# Microcontroller.net
KiCad netlist of a schematic drawn in Altium Designer
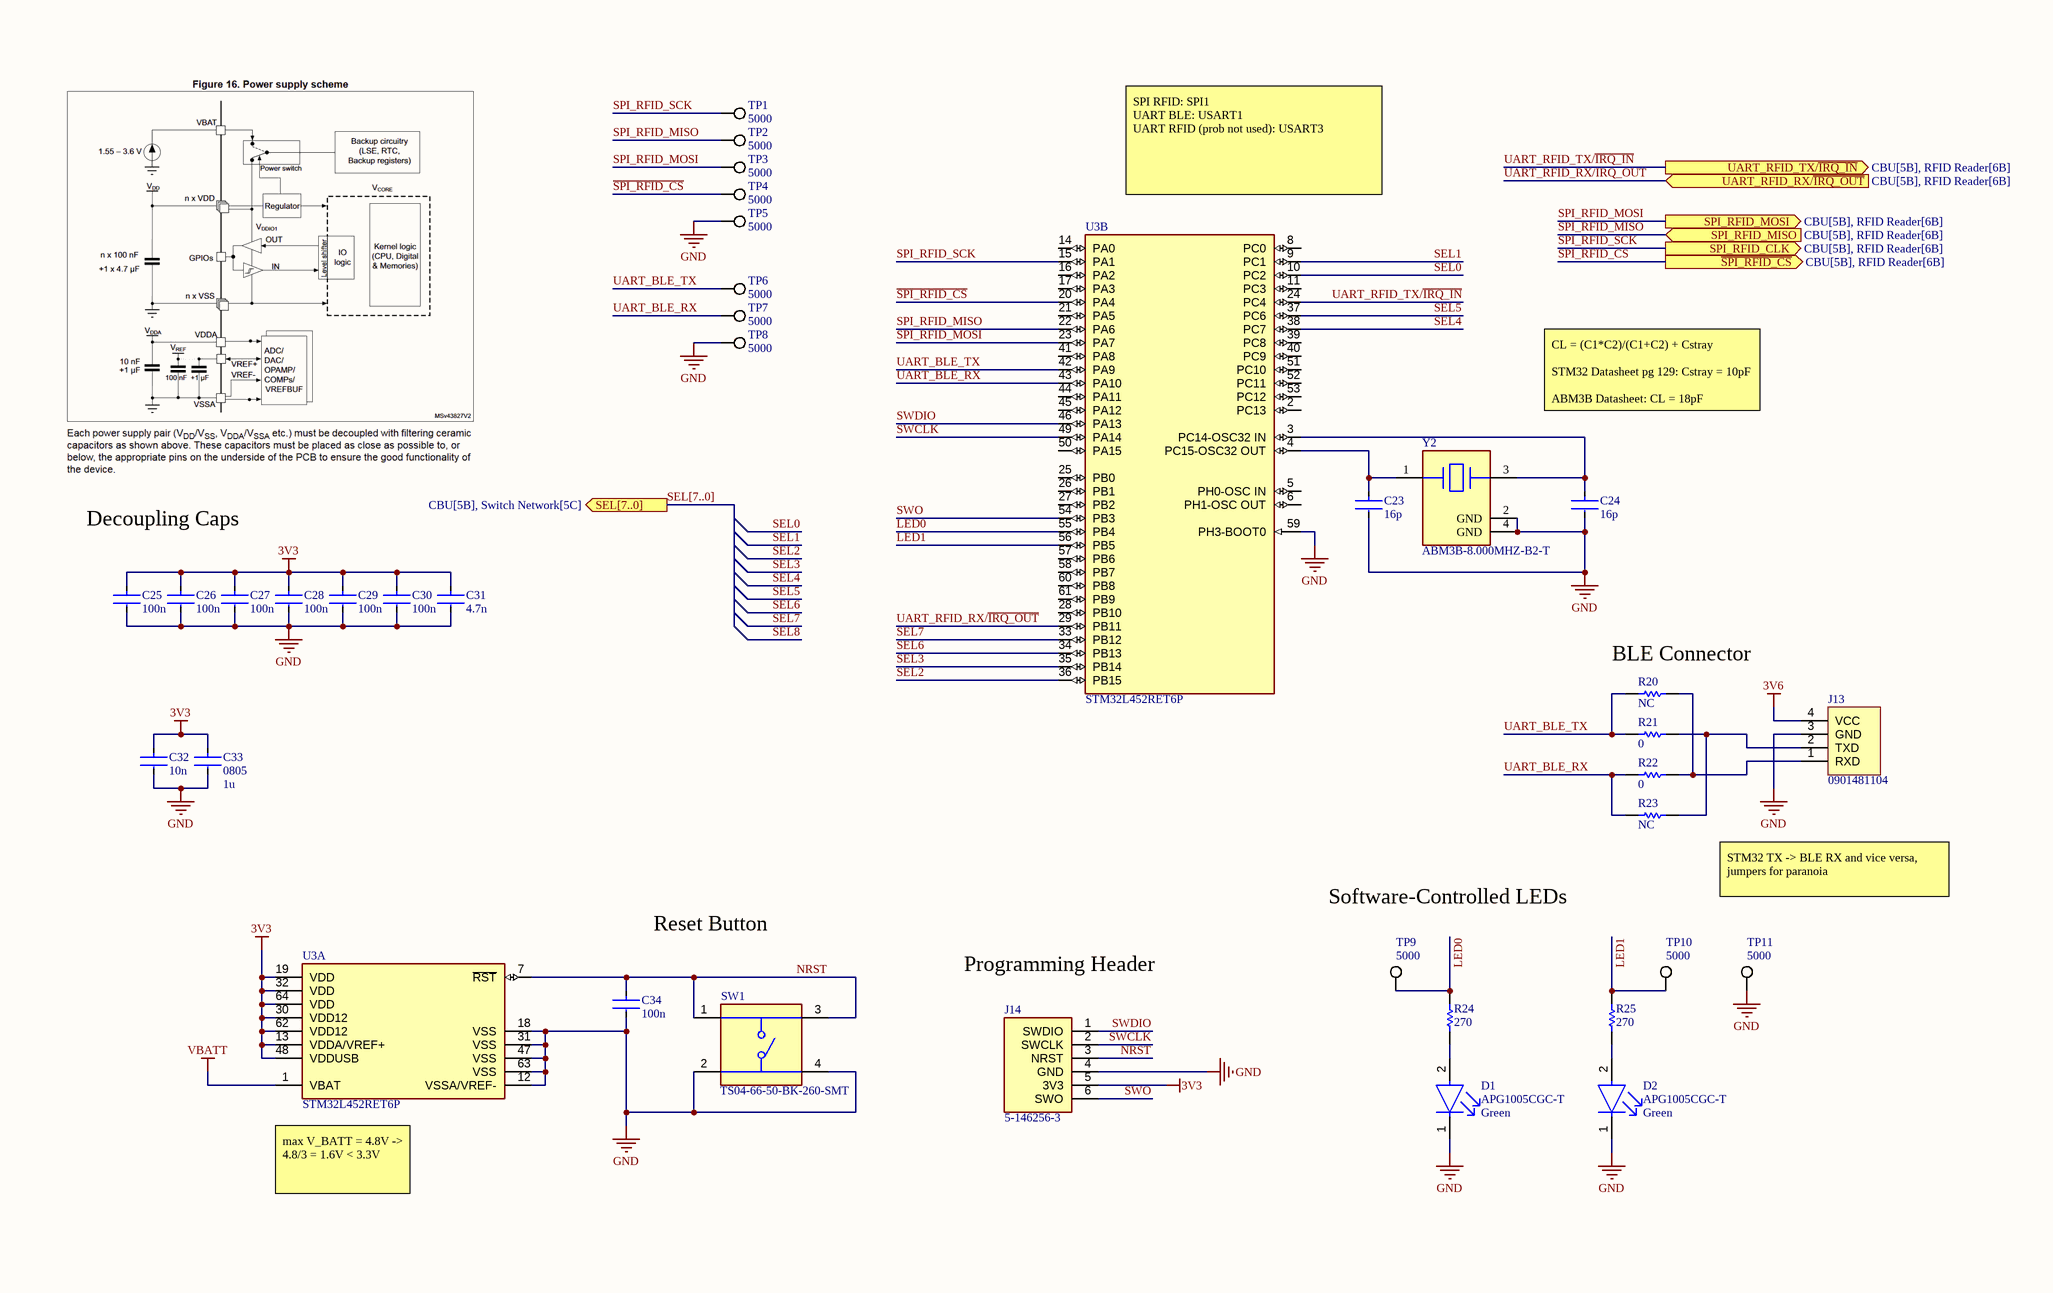
[diagram p0: Microcontroller.SchDoc]

(export (version "E")
  (design (tool "Eeschema 10.0.6"))
  (components
    (comp (ref "C23")
      (value "16p")
      (footprint "FP-0603-Capacitor-CL10-IPC_B")
      (description "CAP CER 50V X7R 0603")
      (fields (field (name "TOLERANCE") "0.1") (field (name "MANUFACTURER") "KEMET"))
      (libsource (lib "CBU-PCB") (part "Ceramic Capacitor 0603"))
    )
    (comp (ref "C24")
      (value "16p")
      (footprint "FP-0603-Capacitor-CL10-IPC_B")
      (description "CAP CER 50V X7R 0603")
      (fields (field (name "TOLERANCE") "0.1") (field (name "MANUFACTURER") "KEMET"))
      (libsource (lib "CBU-PCB") (part "Ceramic Capacitor 0603"))
    )
    (comp (ref "C25")
      (value "100n")
      (footprint "FP-0603-Capacitor-CL10-IPC_B")
      (description "CAP CER 50V X7R 0603")
      (fields (field (name "TOLERANCE") "0.1") (field (name "MANUFACTURER") "KEMET"))
      (libsource (lib "CBU-PCB") (part "Ceramic Capacitor 0603"))
    )
    (comp (ref "C26")
      (value "100n")
      (footprint "FP-0603-Capacitor-CL10-IPC_B")
      (description "CAP CER 50V X7R 0603")
      (fields (field (name "TOLERANCE") "0.1") (field (name "MANUFACTURER") "KEMET"))
      (libsource (lib "CBU-PCB") (part "Ceramic Capacitor 0603"))
    )
    (comp (ref "C27")
      (value "100n")
      (footprint "FP-0603-Capacitor-CL10-IPC_B")
      (description "CAP CER 50V X7R 0603")
      (fields (field (name "TOLERANCE") "0.1") (field (name "MANUFACTURER") "KEMET"))
      (libsource (lib "CBU-PCB") (part "Ceramic Capacitor 0603"))
    )
    (comp (ref "C28")
      (value "100n")
      (footprint "FP-0603-Capacitor-CL10-IPC_B")
      (description "CAP CER 50V X7R 0603")
      (fields (field (name "TOLERANCE") "0.1") (field (name "MANUFACTURER") "KEMET"))
      (libsource (lib "CBU-PCB") (part "Ceramic Capacitor 0603"))
    )
    (comp (ref "C29")
      (value "100n")
      (footprint "FP-0603-Capacitor-CL10-IPC_B")
      (description "CAP CER 50V X7R 0603")
      (fields (field (name "TOLERANCE") "0.1") (field (name "MANUFACTURER") "KEMET"))
      (libsource (lib "CBU-PCB") (part "Ceramic Capacitor 0603"))
    )
    (comp (ref "C30")
      (value "100n")
      (footprint "FP-0603-Capacitor-CL10-IPC_B")
      (description "CAP CER 50V X7R 0603")
      (fields (field (name "TOLERANCE") "0.1") (field (name "MANUFACTURER") "KEMET"))
      (libsource (lib "CBU-PCB") (part "Ceramic Capacitor 0603"))
    )
    (comp (ref "C31")
      (value "4.7n")
      (footprint "FP-0603-Capacitor-CL10-IPC_B")
      (description "CAP CER 50V X7R 0603")
      (fields (field (name "TOLERANCE") "0.1") (field (name "MANUFACTURER") "KEMET"))
      (libsource (lib "CBU-PCB") (part "Ceramic Capacitor 0603"))
    )
    (comp (ref "C32")
      (value "10n")
      (footprint "FP-0603-Capacitor-CL10-IPC_B")
      (description "CAP CER 50V X7R 0603")
      (fields (field (name "TOLERANCE") "0.1") (field (name "MANUFACTURER") "KEMET"))
      (libsource (lib "CBU-PCB") (part "Ceramic Capacitor 0603"))
    )
    (comp (ref "C33")
      (value "1u")
      (footprint "FP-0805-Capacitor-CL21-IPC_B")
      (description "CAP CER 50V X7R 0805")
      (fields
        (field (name "TOLERANCE") "0.1")
        (field (name "MANUFACTURER") "KEMET")
        (field (name "PACKAGE") "0805")
      )
      (libsource (lib "CBU-PCB") (part "Ceramic Capacitor 0805"))
    )
    (comp (ref "C34")
      (value "100n")
      (footprint "FP-0603-Capacitor-CL10-IPC_B")
      (description "CAP CER 50V X7R 0603")
      (fields (field (name "TOLERANCE") "0.1") (field (name "MANUFACTURER") "KEMET"))
      (libsource (lib "CBU-PCB") (part "Ceramic Capacitor 0603"))
    )
    (comp (ref "D1")
      (value "APG1005CGC-T")
      (footprint "FP-APG1005CGC-T-MFG")
      (description "LED GREEN CLEAR CHIP SMD")
      (fields (field (name "COLOR") "Green"))
      (libsource (lib "CBU-PCB") (part "APG1005CGC-T"))
    )
    (comp (ref "D2")
      (value "APG1005CGC-T")
      (footprint "FP-APG1005CGC-T-MFG")
      (description "LED GREEN CLEAR CHIP SMD")
      (fields (field (name "COLOR") "Green"))
      (libsource (lib "CBU-PCB") (part "APG1005CGC-T"))
    )
    (comp (ref "J13")
      (value "0901481104")
      (footprint "0901481104")
      (libsource (lib "CBU-PCB") (part "0901481104"))
    )
    (comp (ref "J14")
      (value "5-146256-3")
      (footprint "TE_5-146256-3")
      (description "Header; Breakaway; 0.100 x 0.100 in.; PC Board; Dual; 6; 0.025 in.; 0.12 in.")
      (fields (field (name "MF") "TE Connectivity") (field (name "DIGI-KEY_PART_NUMBER") "A121369-ND"))
      (libsource (lib "CBU-PCB") (part "5-146256-3"))
    )
    (comp (ref "R20")
      (value "NC")
      (footprint "RESC1608X55X25NL10T15")
      (fields
        (field (name "TOLERANCE") "1%")
        (field (name "MANUFACTURER") "Yageo")
        (field (name "Comment") "RC0603FR-072K2L")
      )
      (libsource (lib "CBU-PCB") (part "Resistor 0603"))
    )
    (comp (ref "R21")
      (value "0")
      (footprint "RESC1608X55X25NL10T15")
      (fields
        (field (name "TOLERANCE") "1%")
        (field (name "MANUFACTURER") "Yageo")
        (field (name "Comment") "RC0603FR-072K2L")
      )
      (libsource (lib "CBU-PCB") (part "Resistor 0603"))
    )
    (comp (ref "R22")
      (value "0")
      (footprint "RESC1608X55X25NL10T15")
      (fields
        (field (name "TOLERANCE") "1%")
        (field (name "MANUFACTURER") "Yageo")
        (field (name "Comment") "RC0603FR-072K2L")
      )
      (libsource (lib "CBU-PCB") (part "Resistor 0603"))
    )
    (comp (ref "R23")
      (value "NC")
      (footprint "RESC1608X55X25NL10T15")
      (fields
        (field (name "TOLERANCE") "1%")
        (field (name "MANUFACTURER") "Yageo")
        (field (name "Comment") "RC0603FR-072K2L")
      )
      (libsource (lib "CBU-PCB") (part "Resistor 0603"))
    )
    (comp (ref "R24")
      (value "270")
      (footprint "RESC1608X55X25NL10T15")
      (fields
        (field (name "TOLERANCE") "1%")
        (field (name "MANUFACTURER") "Yageo")
        (field (name "Comment") "RC0603FR-072K2L")
      )
      (libsource (lib "CBU-PCB") (part "Resistor 0603"))
    )
    (comp (ref "R25")
      (value "270")
      (footprint "RESC1608X55X25NL10T15")
      (fields
        (field (name "TOLERANCE") "1%")
        (field (name "MANUFACTURER") "Yageo")
        (field (name "Comment") "RC0603FR-072K2L")
      )
      (libsource (lib "CBU-PCB") (part "Resistor 0603"))
    )
    (comp (ref "SW1")
      (value "TS04-66-50-BK-260-SMT")
      (footprint "SW_TS04-66-50-BK-260-SMT")
      (description "Tactile Switch SPST-NO Top Actuated Surface Mount")
      (libsource (lib "CBU-PCB") (part "TS04-66-50-BK-260-SMT"))
    )
    (comp (ref "TP1")
      (value "5000")
      (footprint "FP-5000-MFG")
      (description "Red PC Test Point, Miniature Phosphor Bronze Silver Plating Through Hole Mounting Type")
      (libsource (lib "CBU-PCB") (part "5000"))
    )
    (comp (ref "TP2")
      (value "5000")
      (footprint "FP-5000-MFG")
      (description "Red PC Test Point, Miniature Phosphor Bronze Silver Plating Through Hole Mounting Type")
      (libsource (lib "CBU-PCB") (part "5000"))
    )
    (comp (ref "TP3")
      (value "5000")
      (footprint "FP-5000-MFG")
      (description "Red PC Test Point, Miniature Phosphor Bronze Silver Plating Through Hole Mounting Type")
      (libsource (lib "CBU-PCB") (part "5000"))
    )
    (comp (ref "TP4")
      (value "5000")
      (footprint "FP-5000-MFG")
      (description "Red PC Test Point, Miniature Phosphor Bronze Silver Plating Through Hole Mounting Type")
      (libsource (lib "CBU-PCB") (part "5000"))
    )
    (comp (ref "TP5")
      (value "5000")
      (footprint "FP-5000-MFG")
      (description "Red PC Test Point, Miniature Phosphor Bronze Silver Plating Through Hole Mounting Type")
      (libsource (lib "CBU-PCB") (part "5000"))
    )
    (comp (ref "TP6")
      (value "5000")
      (footprint "FP-5000-MFG")
      (description "Red PC Test Point, Miniature Phosphor Bronze Silver Plating Through Hole Mounting Type")
      (libsource (lib "CBU-PCB") (part "5000"))
    )
    (comp (ref "TP7")
      (value "5000")
      (footprint "FP-5000-MFG")
      (description "Red PC Test Point, Miniature Phosphor Bronze Silver Plating Through Hole Mounting Type")
      (libsource (lib "CBU-PCB") (part "5000"))
    )
    (comp (ref "TP8")
      (value "5000")
      (footprint "FP-5000-MFG")
      (description "Red PC Test Point, Miniature Phosphor Bronze Silver Plating Through Hole Mounting Type")
      (libsource (lib "CBU-PCB") (part "5000"))
    )
    (comp (ref "TP9")
      (value "5000")
      (footprint "FP-5000-MFG")
      (description "Red PC Test Point, Miniature Phosphor Bronze Silver Plating Through Hole Mounting Type")
      (libsource (lib "CBU-PCB") (part "5000"))
    )
    (comp (ref "TP10")
      (value "5000")
      (footprint "FP-5000-MFG")
      (description "Red PC Test Point, Miniature Phosphor Bronze Silver Plating Through Hole Mounting Type")
      (libsource (lib "CBU-PCB") (part "5000"))
    )
    (comp (ref "TP11")
      (value "5000")
      (footprint "FP-5000-MFG")
      (description "Red PC Test Point, Miniature Phosphor Bronze Silver Plating Through Hole Mounting Type")
      (libsource (lib "CBU-PCB") (part "5000"))
    )
    (comp (ref "U3")
      (value "STM32L452RET6P")
      (footprint "FP-STM32L452RET6P-MFG")
      (description "IC MCU 32BIT 512KB FLASH 64LQFP")
      (fields
        (field (name "OCTOPART") "https://octopart.com/stm32l452ret6p-stmicroelectronics-82945027")
        (field (name "MANUFACTURER") "STMicroelectronics")
      )
      (libsource (lib "CBU-PCB") (part "STM32L452RET6P"))
    )
    (comp (ref "Y2")
      (value "ABM3B-8.000MHZ-B2-T")
      (footprint "FP-ABM3B-MFG")
      (description "Crystal 8MHz ±20ppm 18pF SMD-4 5mm x 3.2mm")
      (fields (field (name "TOLERANCE") "20ppm"))
      (libsource (lib "CBU-PCB") (part "ABM3B-8.000MHZ-B2-T"))
    )
  )
  (nets
    (net (code "1") (name "/LED0") (class "Default")
      (node (ref "R24") (pin "2") (pinfunction "2_2") (pintype "passive"))
      (node (ref "TP9") (pin "1") (pinfunction "1_1") (pintype "passive"))
      (node (ref "U3") (pin "55") (pinfunction "PB4_55") (pintype "bidirectional"))
    )
    (net (code "2") (name "/LED1") (class "Default")
      (node (ref "R25") (pin "2") (pinfunction "2_2") (pintype "passive"))
      (node (ref "TP10") (pin "1") (pinfunction "1_1") (pintype "passive"))
      (node (ref "U3") (pin "56") (pinfunction "PB5_56") (pintype "bidirectional"))
    )
    (net (code "3") (name "/NRST") (class "Default")
      (node (ref "C34") (pin "1") (pinfunction "1_1") (pintype "passive"))
      (node (ref "J14") (pin "3") (pinfunction "NRST_3") (pintype "passive"))
      (node (ref "SW1") (pin "1") (pinfunction "1_1") (pintype "passive"))
      (node (ref "SW1") (pin "3") (pinfunction "3_3") (pintype "passive"))
      (node (ref "U3") (pin "7") (pinfunction "~{RST}_7") (pintype "bidirectional"))
    )
    (net (code "4") (name "/SEL0") (class "Default")
      (node (ref "U3") (pin "10") (pinfunction "PC2_10") (pintype "bidirectional"))
    )
    (net (code "5") (name "/SEL1") (class "Default")
      (node (ref "U3") (pin "9") (pinfunction "PC1_9") (pintype "bidirectional"))
    )
    (net (code "6") (name "/SEL2") (class "Default")
      (node (ref "U3") (pin "36") (pinfunction "PB15_36") (pintype "bidirectional"))
    )
    (net (code "7") (name "/SEL3") (class "Default")
      (node (ref "U3") (pin "35") (pinfunction "PB14_35") (pintype "bidirectional"))
    )
    (net (code "8") (name "/SEL4") (class "Default")
      (node (ref "U3") (pin "38") (pinfunction "PC7_38") (pintype "bidirectional"))
    )
    (net (code "9") (name "/SEL5") (class "Default")
      (node (ref "U3") (pin "37") (pinfunction "PC6_37") (pintype "bidirectional"))
    )
    (net (code "10") (name "/SEL6") (class "Default")
      (node (ref "U3") (pin "34") (pinfunction "PB13_34") (pintype "bidirectional"))
    )
    (net (code "11") (name "/SEL7") (class "Default")
      (node (ref "U3") (pin "33") (pinfunction "PB12_33") (pintype "bidirectional"))
    )
    (net (code "14") (name "/SPI_RFID_MISO") (class "Default")
      (node (ref "TP2") (pin "1") (pinfunction "1_1") (pintype "passive"))
      (node (ref "U3") (pin "22") (pinfunction "PA6_22") (pintype "bidirectional"))
    )
    (net (code "15") (name "/SPI_RFID_MOSI") (class "Default")
      (node (ref "TP3") (pin "1") (pinfunction "1_1") (pintype "passive"))
      (node (ref "U3") (pin "23") (pinfunction "PA7_23") (pintype "bidirectional"))
    )
    (net (code "16") (name "/SPI_RFID_SCK") (class "Default")
      (node (ref "TP1") (pin "1") (pinfunction "1_1") (pintype "passive"))
      (node (ref "U3") (pin "15") (pinfunction "PA1_15") (pintype "bidirectional"))
    )
    (net (code "17") (name "/SWCLK") (class "Default")
      (node (ref "J14") (pin "2") (pinfunction "SWCLK_2") (pintype "passive"))
      (node (ref "U3") (pin "49") (pinfunction "PA14_49") (pintype "bidirectional"))
    )
    (net (code "18") (name "/SWDIO") (class "Default")
      (node (ref "J14") (pin "1") (pinfunction "SWDIO_1") (pintype "passive"))
      (node (ref "U3") (pin "46") (pinfunction "PA13_46") (pintype "bidirectional"))
    )
    (net (code "19") (name "/SWO") (class "Default")
      (node (ref "J14") (pin "6") (pinfunction "SWO_6") (pintype "passive"))
      (node (ref "U3") (pin "54") (pinfunction "PB3_54") (pintype "bidirectional"))
    )
    (net (code "20") (name "/UART_BLE_RX") (class "Default")
      (node (ref "R22") (pin "2") (pinfunction "2_2") (pintype "passive"))
      (node (ref "R23") (pin "1") (pinfunction "1_1") (pintype "passive"))
      (node (ref "TP7") (pin "1") (pinfunction "1_1") (pintype "passive"))
      (node (ref "U3") (pin "43") (pinfunction "PA10_43") (pintype "bidirectional"))
    )
    (net (code "21") (name "/UART_BLE_TX") (class "Default")
      (node (ref "R20") (pin "2") (pinfunction "2_2") (pintype "passive"))
      (node (ref "R21") (pin "1") (pinfunction "1_1") (pintype "passive"))
      (node (ref "TP6") (pin "1") (pinfunction "1_1") (pintype "passive"))
      (node (ref "U3") (pin "42") (pinfunction "PA9_42") (pintype "bidirectional"))
    )
    (net (code "22") (name "/UART_RFID_RX{slash}~{IRQ_OUT}") (class "Default")
      (node (ref "U3") (pin "29") (pinfunction "PB11_29") (pintype "bidirectional"))
    )
    (net (code "23") (name "/UART_RFID_TX{slash}~{IRQ_IN}") (class "Default")
      (node (ref "U3") (pin "24") (pinfunction "PC4_24") (pintype "bidirectional"))
    )
    (net (code "24") (name "/~{SPI_RFID_CS}") (class "Default")
      (node (ref "TP4") (pin "1") (pinfunction "1_1") (pintype "passive"))
      (node (ref "U3") (pin "20") (pinfunction "PA4_20") (pintype "bidirectional"))
    )
    (net (code "25") (name "3V3") (class "Default")
      (node (ref "C25") (pin "1") (pinfunction "1_1") (pintype "passive"))
      (node (ref "C26") (pin "1") (pinfunction "1_1") (pintype "passive"))
      (node (ref "C27") (pin "1") (pinfunction "1_1") (pintype "passive"))
      (node (ref "C28") (pin "1") (pinfunction "1_1") (pintype "passive"))
      (node (ref "C29") (pin "1") (pinfunction "1_1") (pintype "passive"))
      (node (ref "C30") (pin "1") (pinfunction "1_1") (pintype "passive"))
      (node (ref "C31") (pin "1") (pinfunction "1_1") (pintype "passive"))
      (node (ref "C32") (pin "1") (pinfunction "1_1") (pintype "passive"))
      (node (ref "C33") (pin "1") (pinfunction "1_1") (pintype "passive"))
      (node (ref "J14") (pin "5") (pinfunction "3V3_5") (pintype "passive"))
      (node (ref "U3") (pin "13") (pinfunction "VDDA/VREF+_13") (pintype "power_in"))
      (node (ref "U3") (pin "19") (pinfunction "VDD_19") (pintype "power_in"))
      (node (ref "U3") (pin "30") (pinfunction "VDD12_30") (pintype "power_in"))
      (node (ref "U3") (pin "32") (pinfunction "VDD_32") (pintype "power_in"))
      (node (ref "U3") (pin "48") (pinfunction "VDDUSB_48") (pintype "power_in"))
      (node (ref "U3") (pin "62") (pinfunction "VDD12_62") (pintype "power_in"))
      (node (ref "U3") (pin "64") (pinfunction "VDD_64") (pintype "power_in"))
    )
    (net (code "26") (name "3V6") (class "Default")
      (node (ref "J13") (pin "4") (pinfunction "VCC_4") (pintype "passive"))
    )
    (net (code "27") (name "GND") (class "Default")
      (node (ref "C23") (pin "2") (pinfunction "2_2") (pintype "passive"))
      (node (ref "C24") (pin "2") (pinfunction "2_2") (pintype "passive"))
      (node (ref "C25") (pin "2") (pinfunction "2_2") (pintype "passive"))
      (node (ref "C26") (pin "2") (pinfunction "2_2") (pintype "passive"))
      (node (ref "C27") (pin "2") (pinfunction "2_2") (pintype "passive"))
      (node (ref "C28") (pin "2") (pinfunction "2_2") (pintype "passive"))
      (node (ref "C29") (pin "2") (pinfunction "2_2") (pintype "passive"))
      (node (ref "C30") (pin "2") (pinfunction "2_2") (pintype "passive"))
      (node (ref "C31") (pin "2") (pinfunction "2_2") (pintype "passive"))
      (node (ref "C32") (pin "2") (pinfunction "2_2") (pintype "passive"))
      (node (ref "C33") (pin "2") (pinfunction "2_2") (pintype "passive"))
      (node (ref "C34") (pin "2") (pinfunction "2_2") (pintype "passive"))
      (node (ref "D1") (pin "1") (pinfunction "C_1") (pintype "passive"))
      (node (ref "D2") (pin "1") (pinfunction "C_1") (pintype "passive"))
      (node (ref "J13") (pin "3") (pinfunction "GND_3") (pintype "passive"))
      (node (ref "J14") (pin "4") (pinfunction "GND_4") (pintype "passive"))
      (node (ref "SW1") (pin "2") (pinfunction "2_2") (pintype "passive"))
      (node (ref "SW1") (pin "4") (pinfunction "4_4") (pintype "passive"))
      (node (ref "TP11") (pin "1") (pinfunction "1_1") (pintype "passive"))
      (node (ref "TP5") (pin "1") (pinfunction "1_1") (pintype "passive"))
      (node (ref "TP8") (pin "1") (pinfunction "1_1") (pintype "passive"))
      (node (ref "U3") (pin "12") (pinfunction "VSSA/VREF-_12") (pintype "power_in"))
      (node (ref "U3") (pin "18") (pinfunction "VSS_18") (pintype "power_in"))
      (node (ref "U3") (pin "31") (pinfunction "VSS_31") (pintype "power_in"))
      (node (ref "U3") (pin "47") (pinfunction "VSS_47") (pintype "power_in"))
      (node (ref "U3") (pin "59") (pinfunction "PH3-BOOT0_59") (pintype "input"))
      (node (ref "U3") (pin "63") (pinfunction "VSS_63") (pintype "power_in"))
      (node (ref "Y2") (pin "2") (pinfunction "GND_2") (pintype "power_in"))
      (node (ref "Y2") (pin "4") (pinfunction "GND_4") (pintype "power_in"))
    )
    (net (code "28") (name "Net-(D1-A)") (class "Default")
      (node (ref "D1") (pin "2") (pinfunction "A_2") (pintype "passive"))
      (node (ref "R24") (pin "1") (pinfunction "1_1") (pintype "passive"))
    )
    (net (code "29") (name "Net-(D2-A)") (class "Default")
      (node (ref "D2") (pin "2") (pinfunction "A_2") (pintype "passive"))
      (node (ref "R25") (pin "1") (pinfunction "1_1") (pintype "passive"))
    )
    (net (code "30") (name "Net-(J13-RXD)") (class "Default")
      (node (ref "J13") (pin "1") (pinfunction "RXD_1") (pintype "passive"))
      (node (ref "R20") (pin "1") (pinfunction "1_1") (pintype "passive"))
      (node (ref "R22") (pin "1") (pinfunction "1_1") (pintype "passive"))
    )
    (net (code "31") (name "Net-(J13-TXD)") (class "Default")
      (node (ref "J13") (pin "2") (pinfunction "TXD_2") (pintype "passive"))
      (node (ref "R21") (pin "2") (pinfunction "2_2") (pintype "passive"))
      (node (ref "R23") (pin "2") (pinfunction "2_2") (pintype "passive"))
    )
    (net (code "32") (name "Net-(U3B-PC14-OSC32_IN)") (class "Default")
      (node (ref "C24") (pin "1") (pinfunction "1_1") (pintype "passive"))
      (node (ref "U3") (pin "3") (pinfunction "PC14-OSC32_IN_3") (pintype "bidirectional"))
      (node (ref "Y2") (pin "3") (pinfunction "3_3") (pintype "passive"))
    )
    (net (code "33") (name "Net-(U3B-PC15-OSC32_OUT)") (class "Default")
      (node (ref "C23") (pin "1") (pinfunction "1_1") (pintype "passive"))
      (node (ref "U3") (pin "4") (pinfunction "PC15-OSC32_OUT_4") (pintype "bidirectional"))
      (node (ref "Y2") (pin "1") (pinfunction "1_1") (pintype "passive"))
    )
    (net (code "34") (name "VBATT") (class "Default")
      (node (ref "U3") (pin "1") (pinfunction "VBAT_1") (pintype "power_in"))
    )
    (net (code "35") (name "unconnected-(U3B-PA0-Pad14)") (class "Default")
      (node (ref "U3") (pin "14") (pinfunction "PA0_14") (pintype "bidirectional"))
    )
    (net (code "36") (name "unconnected-(U3B-PA2-Pad16)") (class "Default")
      (node (ref "U3") (pin "16") (pinfunction "PA2_16") (pintype "bidirectional"))
    )
    (net (code "37") (name "unconnected-(U3B-PA3-Pad17)") (class "Default")
      (node (ref "U3") (pin "17") (pinfunction "PA3_17") (pintype "bidirectional"))
    )
    (net (code "38") (name "unconnected-(U3B-PA5-Pad21)") (class "Default")
      (node (ref "U3") (pin "21") (pinfunction "PA5_21") (pintype "bidirectional"))
    )
    (net (code "39") (name "unconnected-(U3B-PA8-Pad41)") (class "Default")
      (node (ref "U3") (pin "41") (pinfunction "PA8_41") (pintype "bidirectional"))
    )
    (net (code "40") (name "unconnected-(U3B-PA11-Pad44)") (class "Default")
      (node (ref "U3") (pin "44") (pinfunction "PA11_44") (pintype "bidirectional"))
    )
    (net (code "41") (name "unconnected-(U3B-PA12-Pad45)") (class "Default")
      (node (ref "U3") (pin "45") (pinfunction "PA12_45") (pintype "bidirectional"))
    )
    (net (code "42") (name "unconnected-(U3B-PA15-Pad50)") (class "Default")
      (node (ref "U3") (pin "50") (pinfunction "PA15_50") (pintype "bidirectional"))
    )
    (net (code "43") (name "unconnected-(U3B-PB0-Pad25)") (class "Default")
      (node (ref "U3") (pin "25") (pinfunction "PB0_25") (pintype "bidirectional"))
    )
    (net (code "44") (name "unconnected-(U3B-PB1-Pad26)") (class "Default")
      (node (ref "U3") (pin "26") (pinfunction "PB1_26") (pintype "bidirectional"))
    )
    (net (code "45") (name "unconnected-(U3B-PB2-Pad27)") (class "Default")
      (node (ref "U3") (pin "27") (pinfunction "PB2_27") (pintype "bidirectional"))
    )
    (net (code "46") (name "unconnected-(U3B-PB6-Pad57)") (class "Default")
      (node (ref "U3") (pin "57") (pinfunction "PB6_57") (pintype "bidirectional"))
    )
    (net (code "47") (name "unconnected-(U3B-PB7-Pad58)") (class "Default")
      (node (ref "U3") (pin "58") (pinfunction "PB7_58") (pintype "bidirectional"))
    )
    (net (code "48") (name "unconnected-(U3B-PB8-Pad60)") (class "Default")
      (node (ref "U3") (pin "60") (pinfunction "PB8_60") (pintype "bidirectional"))
    )
    (net (code "49") (name "unconnected-(U3B-PB9-Pad61)") (class "Default")
      (node (ref "U3") (pin "61") (pinfunction "PB9_61") (pintype "bidirectional"))
    )
    (net (code "50") (name "unconnected-(U3B-PB10-Pad28)") (class "Default")
      (node (ref "U3") (pin "28") (pinfunction "PB10_28") (pintype "bidirectional"))
    )
    (net (code "51") (name "unconnected-(U3B-PC0-Pad8)") (class "Default")
      (node (ref "U3") (pin "8") (pinfunction "PC0_8") (pintype "bidirectional"))
    )
    (net (code "52") (name "unconnected-(U3B-PC3-Pad11)") (class "Default")
      (node (ref "U3") (pin "11") (pinfunction "PC3_11") (pintype "bidirectional"))
    )
    (net (code "53") (name "unconnected-(U3B-PC8-Pad39)") (class "Default")
      (node (ref "U3") (pin "39") (pinfunction "PC8_39") (pintype "bidirectional"))
    )
    (net (code "54") (name "unconnected-(U3B-PC9-Pad40)") (class "Default")
      (node (ref "U3") (pin "40") (pinfunction "PC9_40") (pintype "bidirectional"))
    )
    (net (code "55") (name "unconnected-(U3B-PC10-Pad51)") (class "Default")
      (node (ref "U3") (pin "51") (pinfunction "PC10_51") (pintype "bidirectional"))
    )
    (net (code "56") (name "unconnected-(U3B-PC11-Pad52)") (class "Default")
      (node (ref "U3") (pin "52") (pinfunction "PC11_52") (pintype "bidirectional"))
    )
    (net (code "57") (name "unconnected-(U3B-PC12-Pad53)") (class "Default")
      (node (ref "U3") (pin "53") (pinfunction "PC12_53") (pintype "bidirectional"))
    )
    (net (code "58") (name "unconnected-(U3B-PC13-Pad2)") (class "Default")
      (node (ref "U3") (pin "2") (pinfunction "PC13_2") (pintype "bidirectional"))
    )
    (net (code "59") (name "unconnected-(U3B-PH0-OSC_IN-Pad5)") (class "Default")
      (node (ref "U3") (pin "5") (pinfunction "PH0-OSC_IN_5") (pintype "bidirectional"))
    )
    (net (code "60") (name "unconnected-(U3B-PH1-OSC_OUT-Pad6)") (class "Default")
      (node (ref "U3") (pin "6") (pinfunction "PH1-OSC_OUT_6") (pintype "bidirectional"))
    )
  )
)
